# f407.net
KiCad netlist of a schematic drawn in EasyEDA Pro
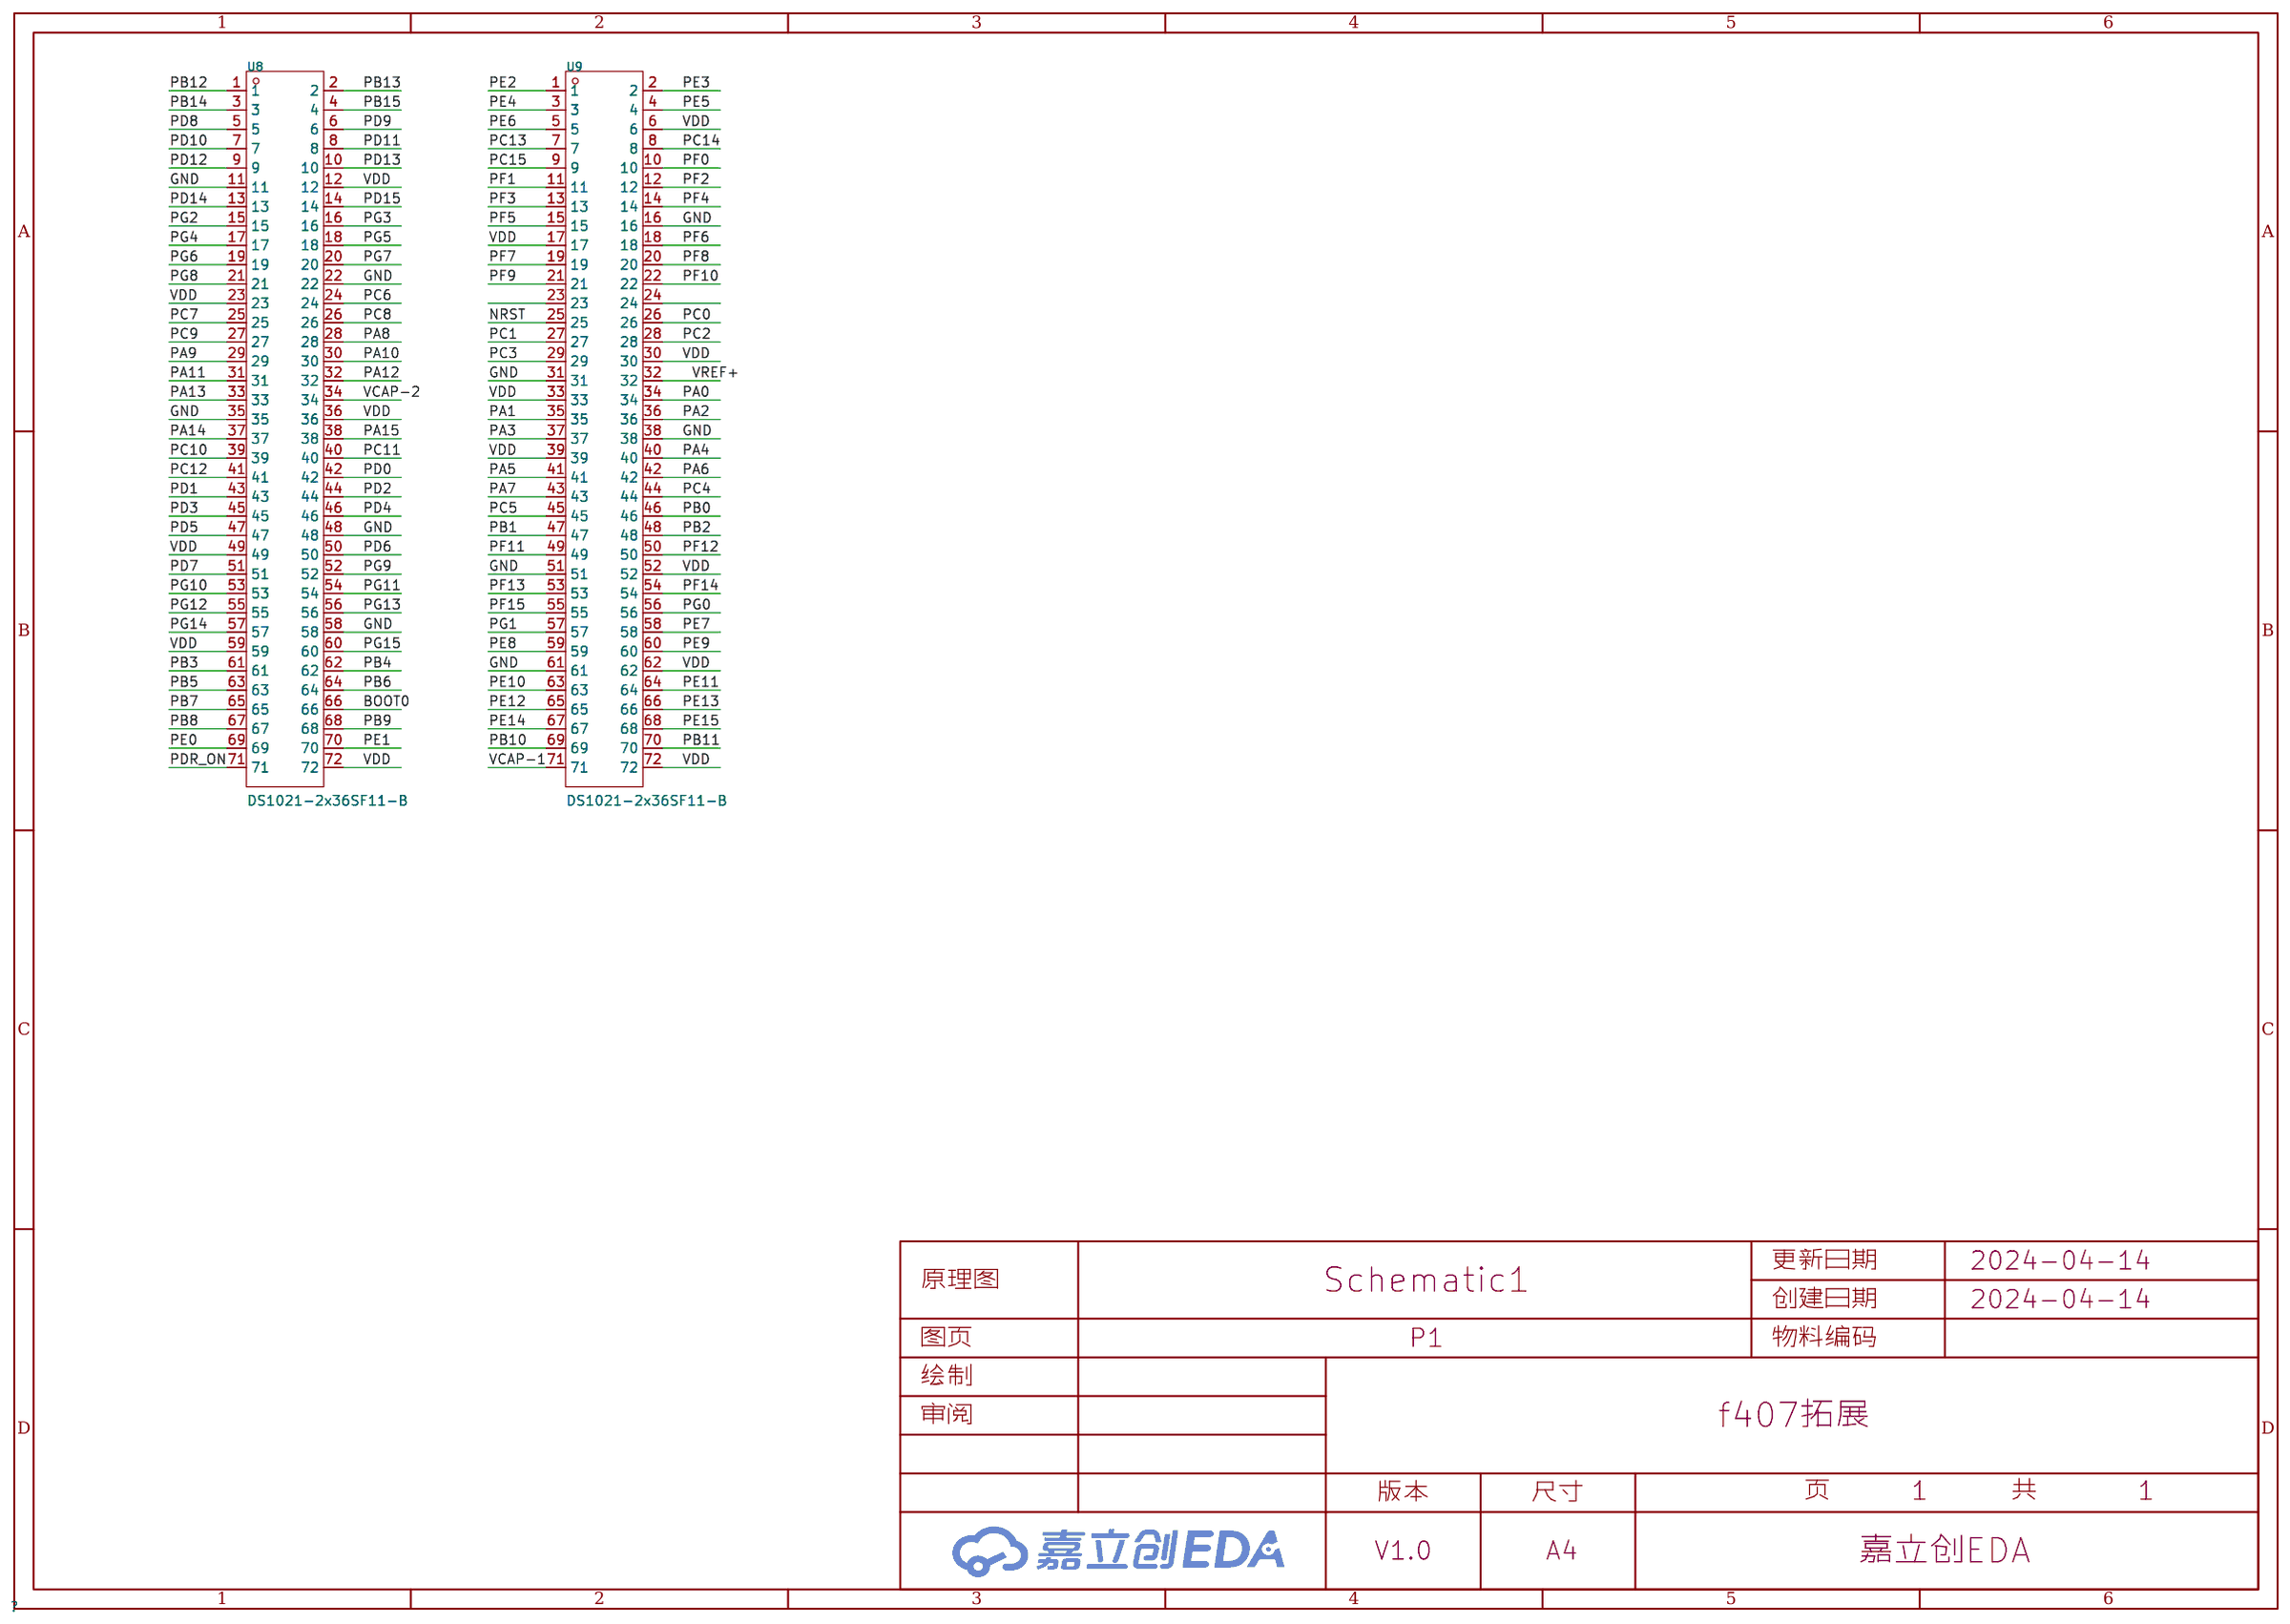
[diagram p0: schematic sheet]

(export (version "E")
  (design (tool "Eeschema 10.0.6"))
  (components
    (comp (ref "U8")
      (value "DS1021-2x36SF11-B")
      (footprint "easyedapro:HDR-TH_72P-P2.54-V-M-R2-C36-S2.54")
      (description "插针结构:2x36P;间距:2.54mm;安装类型:直插;排数:双排;总PIN位数:72P;")
      (fields (field (name "Manufacturer") "CONNFLY"))
      (libsource (lib "easyedapro") (part "DS1021-2X36SF11-B"))
    )
    (comp (ref "U9")
      (value "DS1021-2x36SF11-B")
      (footprint "easyedapro:HDR-TH_72P-P2.54-V-M-R2-C36-S2.54")
      (description "插针结构:2x36P;间距:2.54mm;安装类型:直插;排数:双排;总PIN位数:72P;")
      (fields (field (name "Manufacturer") "CONNFLY"))
      (libsource (lib "easyedapro") (part "DS1021-2X36SF11-B"))
    )
  )
  (nets
    (net (code "1") (name "/BOOT0") (class "Default")
      (node (ref "U8") (pin "66") (pinfunction "66_66") (pintype "input"))
    )
    (net (code "2") (name "/GND") (class "Default")
      (node (ref "U8") (pin "11") (pinfunction "11_11") (pintype "input"))
      (node (ref "U8") (pin "22") (pinfunction "22_22") (pintype "input"))
      (node (ref "U8") (pin "35") (pinfunction "35_35") (pintype "input"))
      (node (ref "U8") (pin "48") (pinfunction "48_48") (pintype "input"))
      (node (ref "U8") (pin "58") (pinfunction "58_58") (pintype "input"))
      (node (ref "U9") (pin "16") (pinfunction "16_16") (pintype "input"))
      (node (ref "U9") (pin "31") (pinfunction "31_31") (pintype "input"))
      (node (ref "U9") (pin "38") (pinfunction "38_38") (pintype "input"))
      (node (ref "U9") (pin "51") (pinfunction "51_51") (pintype "input"))
      (node (ref "U9") (pin "61") (pinfunction "61_61") (pintype "input"))
    )
    (net (code "3") (name "/NRST") (class "Default")
      (node (ref "U9") (pin "25") (pinfunction "25_25") (pintype "input"))
    )
    (net (code "4") (name "/PA0") (class "Default")
      (node (ref "U9") (pin "34") (pinfunction "34_34") (pintype "input"))
    )
    (net (code "5") (name "/PA1") (class "Default")
      (node (ref "U9") (pin "35") (pinfunction "35_35") (pintype "input"))
    )
    (net (code "6") (name "/PA2") (class "Default")
      (node (ref "U9") (pin "36") (pinfunction "36_36") (pintype "input"))
    )
    (net (code "7") (name "/PA3") (class "Default")
      (node (ref "U9") (pin "37") (pinfunction "37_37") (pintype "input"))
    )
    (net (code "8") (name "/PA4") (class "Default")
      (node (ref "U9") (pin "40") (pinfunction "40_40") (pintype "input"))
    )
    (net (code "9") (name "/PA5") (class "Default")
      (node (ref "U9") (pin "41") (pinfunction "41_41") (pintype "input"))
    )
    (net (code "10") (name "/PA6") (class "Default")
      (node (ref "U9") (pin "42") (pinfunction "42_42") (pintype "input"))
    )
    (net (code "11") (name "/PA7") (class "Default")
      (node (ref "U9") (pin "43") (pinfunction "43_43") (pintype "input"))
    )
    (net (code "12") (name "/PA8") (class "Default")
      (node (ref "U8") (pin "28") (pinfunction "28_28") (pintype "input"))
    )
    (net (code "13") (name "/PA9") (class "Default")
      (node (ref "U8") (pin "29") (pinfunction "29_29") (pintype "input"))
    )
    (net (code "14") (name "/PA10") (class "Default")
      (node (ref "U8") (pin "30") (pinfunction "30_30") (pintype "input"))
    )
    (net (code "15") (name "/PA11") (class "Default")
      (node (ref "U8") (pin "31") (pinfunction "31_31") (pintype "input"))
    )
    (net (code "16") (name "/PA12") (class "Default")
      (node (ref "U8") (pin "32") (pinfunction "32_32") (pintype "input"))
    )
    (net (code "17") (name "/PA13") (class "Default")
      (node (ref "U8") (pin "33") (pinfunction "33_33") (pintype "input"))
    )
    (net (code "18") (name "/PA14") (class "Default")
      (node (ref "U8") (pin "37") (pinfunction "37_37") (pintype "input"))
    )
    (net (code "19") (name "/PA15") (class "Default")
      (node (ref "U8") (pin "38") (pinfunction "38_38") (pintype "input"))
    )
    (net (code "20") (name "/PB0") (class "Default")
      (node (ref "U9") (pin "46") (pinfunction "46_46") (pintype "input"))
    )
    (net (code "21") (name "/PB1") (class "Default")
      (node (ref "U9") (pin "47") (pinfunction "47_47") (pintype "input"))
    )
    (net (code "22") (name "/PB2") (class "Default")
      (node (ref "U9") (pin "48") (pinfunction "48_48") (pintype "input"))
    )
    (net (code "23") (name "/PB3") (class "Default")
      (node (ref "U8") (pin "61") (pinfunction "61_61") (pintype "input"))
    )
    (net (code "24") (name "/PB4") (class "Default")
      (node (ref "U8") (pin "62") (pinfunction "62_62") (pintype "input"))
    )
    (net (code "25") (name "/PB5") (class "Default")
      (node (ref "U8") (pin "63") (pinfunction "63_63") (pintype "input"))
    )
    (net (code "26") (name "/PB6") (class "Default")
      (node (ref "U8") (pin "64") (pinfunction "64_64") (pintype "input"))
    )
    (net (code "27") (name "/PB7") (class "Default")
      (node (ref "U8") (pin "65") (pinfunction "65_65") (pintype "input"))
    )
    (net (code "28") (name "/PB8") (class "Default")
      (node (ref "U8") (pin "67") (pinfunction "67_67") (pintype "input"))
    )
    (net (code "29") (name "/PB9") (class "Default")
      (node (ref "U8") (pin "68") (pinfunction "68_68") (pintype "input"))
    )
    (net (code "30") (name "/PB10") (class "Default")
      (node (ref "U9") (pin "69") (pinfunction "69_69") (pintype "input"))
    )
    (net (code "31") (name "/PB11") (class "Default")
      (node (ref "U9") (pin "70") (pinfunction "70_70") (pintype "input"))
    )
    (net (code "32") (name "/PB12") (class "Default")
      (node (ref "U8") (pin "1") (pinfunction "1_1") (pintype "input"))
    )
    (net (code "33") (name "/PB13") (class "Default")
      (node (ref "U8") (pin "2") (pinfunction "2_2") (pintype "input"))
    )
    (net (code "34") (name "/PB14") (class "Default")
      (node (ref "U8") (pin "3") (pinfunction "3_3") (pintype "input"))
    )
    (net (code "35") (name "/PB15") (class "Default")
      (node (ref "U8") (pin "4") (pinfunction "4_4") (pintype "input"))
    )
    (net (code "36") (name "/PC0") (class "Default")
      (node (ref "U9") (pin "26") (pinfunction "26_26") (pintype "input"))
    )
    (net (code "37") (name "/PC1") (class "Default")
      (node (ref "U9") (pin "27") (pinfunction "27_27") (pintype "input"))
    )
    (net (code "38") (name "/PC2") (class "Default")
      (node (ref "U9") (pin "28") (pinfunction "28_28") (pintype "input"))
    )
    (net (code "39") (name "/PC3") (class "Default")
      (node (ref "U9") (pin "29") (pinfunction "29_29") (pintype "input"))
    )
    (net (code "40") (name "/PC4") (class "Default")
      (node (ref "U9") (pin "44") (pinfunction "44_44") (pintype "input"))
    )
    (net (code "41") (name "/PC5") (class "Default")
      (node (ref "U9") (pin "45") (pinfunction "45_45") (pintype "input"))
    )
    (net (code "42") (name "/PC6") (class "Default")
      (node (ref "U8") (pin "24") (pinfunction "24_24") (pintype "input"))
    )
    (net (code "43") (name "/PC7") (class "Default")
      (node (ref "U8") (pin "25") (pinfunction "25_25") (pintype "input"))
    )
    (net (code "44") (name "/PC8") (class "Default")
      (node (ref "U8") (pin "26") (pinfunction "26_26") (pintype "input"))
    )
    (net (code "45") (name "/PC9") (class "Default")
      (node (ref "U8") (pin "27") (pinfunction "27_27") (pintype "input"))
    )
    (net (code "46") (name "/PC10") (class "Default")
      (node (ref "U8") (pin "39") (pinfunction "39_39") (pintype "input"))
    )
    (net (code "47") (name "/PC11") (class "Default")
      (node (ref "U8") (pin "40") (pinfunction "40_40") (pintype "input"))
    )
    (net (code "48") (name "/PC12") (class "Default")
      (node (ref "U8") (pin "41") (pinfunction "41_41") (pintype "input"))
    )
    (net (code "49") (name "/PC13") (class "Default")
      (node (ref "U9") (pin "7") (pinfunction "7_7") (pintype "input"))
    )
    (net (code "50") (name "/PC14") (class "Default")
      (node (ref "U9") (pin "8") (pinfunction "8_8") (pintype "input"))
    )
    (net (code "51") (name "/PC15") (class "Default")
      (node (ref "U9") (pin "9") (pinfunction "9_9") (pintype "input"))
    )
    (net (code "52") (name "/PD0") (class "Default")
      (node (ref "U8") (pin "42") (pinfunction "42_42") (pintype "input"))
    )
    (net (code "53") (name "/PD1") (class "Default")
      (node (ref "U8") (pin "43") (pinfunction "43_43") (pintype "input"))
    )
    (net (code "54") (name "/PD2") (class "Default")
      (node (ref "U8") (pin "44") (pinfunction "44_44") (pintype "input"))
    )
    (net (code "55") (name "/PD3") (class "Default")
      (node (ref "U8") (pin "45") (pinfunction "45_45") (pintype "input"))
    )
    (net (code "56") (name "/PD4") (class "Default")
      (node (ref "U8") (pin "46") (pinfunction "46_46") (pintype "input"))
    )
    (net (code "57") (name "/PD5") (class "Default")
      (node (ref "U8") (pin "47") (pinfunction "47_47") (pintype "input"))
    )
    (net (code "58") (name "/PD6") (class "Default")
      (node (ref "U8") (pin "50") (pinfunction "50_50") (pintype "input"))
    )
    (net (code "59") (name "/PD7") (class "Default")
      (node (ref "U8") (pin "51") (pinfunction "51_51") (pintype "input"))
    )
    (net (code "60") (name "/PD8") (class "Default")
      (node (ref "U8") (pin "5") (pinfunction "5_5") (pintype "input"))
    )
    (net (code "61") (name "/PD9") (class "Default")
      (node (ref "U8") (pin "6") (pinfunction "6_6") (pintype "input"))
    )
    (net (code "62") (name "/PD10") (class "Default")
      (node (ref "U8") (pin "7") (pinfunction "7_7") (pintype "input"))
    )
    (net (code "63") (name "/PD11") (class "Default")
      (node (ref "U8") (pin "8") (pinfunction "8_8") (pintype "input"))
    )
    (net (code "64") (name "/PD12") (class "Default")
      (node (ref "U8") (pin "9") (pinfunction "9_9") (pintype "input"))
    )
    (net (code "65") (name "/PD13") (class "Default")
      (node (ref "U8") (pin "10") (pinfunction "10_10") (pintype "input"))
    )
    (net (code "66") (name "/PD14") (class "Default")
      (node (ref "U8") (pin "13") (pinfunction "13_13") (pintype "input"))
    )
    (net (code "67") (name "/PD15") (class "Default")
      (node (ref "U8") (pin "14") (pinfunction "14_14") (pintype "input"))
    )
    (net (code "68") (name "/PDR_ON") (class "Default")
      (node (ref "U8") (pin "71") (pinfunction "71_71") (pintype "input"))
    )
    (net (code "69") (name "/PE0") (class "Default")
      (node (ref "U8") (pin "69") (pinfunction "69_69") (pintype "input"))
    )
    (net (code "70") (name "/PE1") (class "Default")
      (node (ref "U8") (pin "70") (pinfunction "70_70") (pintype "input"))
    )
    (net (code "71") (name "/PE2") (class "Default")
      (node (ref "U9") (pin "1") (pinfunction "1_1") (pintype "input"))
    )
    (net (code "72") (name "/PE3") (class "Default")
      (node (ref "U9") (pin "2") (pinfunction "2_2") (pintype "input"))
    )
    (net (code "73") (name "/PE4") (class "Default")
      (node (ref "U9") (pin "3") (pinfunction "3_3") (pintype "input"))
    )
    (net (code "74") (name "/PE5") (class "Default")
      (node (ref "U9") (pin "4") (pinfunction "4_4") (pintype "input"))
    )
    (net (code "75") (name "/PE6") (class "Default")
      (node (ref "U9") (pin "5") (pinfunction "5_5") (pintype "input"))
    )
    (net (code "76") (name "/PE7") (class "Default")
      (node (ref "U9") (pin "58") (pinfunction "58_58") (pintype "input"))
    )
    (net (code "77") (name "/PE8") (class "Default")
      (node (ref "U9") (pin "59") (pinfunction "59_59") (pintype "input"))
    )
    (net (code "78") (name "/PE9") (class "Default")
      (node (ref "U9") (pin "60") (pinfunction "60_60") (pintype "input"))
    )
    (net (code "79") (name "/PE10") (class "Default")
      (node (ref "U9") (pin "63") (pinfunction "63_63") (pintype "input"))
    )
    (net (code "80") (name "/PE11") (class "Default")
      (node (ref "U9") (pin "64") (pinfunction "64_64") (pintype "input"))
    )
    (net (code "81") (name "/PE12") (class "Default")
      (node (ref "U9") (pin "65") (pinfunction "65_65") (pintype "input"))
    )
    (net (code "82") (name "/PE13") (class "Default")
      (node (ref "U9") (pin "66") (pinfunction "66_66") (pintype "input"))
    )
    (net (code "83") (name "/PE14") (class "Default")
      (node (ref "U9") (pin "67") (pinfunction "67_67") (pintype "input"))
    )
    (net (code "84") (name "/PE15") (class "Default")
      (node (ref "U9") (pin "68") (pinfunction "68_68") (pintype "input"))
    )
    (net (code "85") (name "/PF0") (class "Default")
      (node (ref "U9") (pin "10") (pinfunction "10_10") (pintype "input"))
    )
    (net (code "86") (name "/PF1") (class "Default")
      (node (ref "U9") (pin "11") (pinfunction "11_11") (pintype "input"))
    )
    (net (code "87") (name "/PF2") (class "Default")
      (node (ref "U9") (pin "12") (pinfunction "12_12") (pintype "input"))
    )
    (net (code "88") (name "/PF3") (class "Default")
      (node (ref "U9") (pin "13") (pinfunction "13_13") (pintype "input"))
    )
    (net (code "89") (name "/PF4") (class "Default")
      (node (ref "U9") (pin "14") (pinfunction "14_14") (pintype "input"))
    )
    (net (code "90") (name "/PF5") (class "Default")
      (node (ref "U9") (pin "15") (pinfunction "15_15") (pintype "input"))
    )
    (net (code "91") (name "/PF6") (class "Default")
      (node (ref "U9") (pin "18") (pinfunction "18_18") (pintype "input"))
    )
    (net (code "92") (name "/PF7") (class "Default")
      (node (ref "U9") (pin "19") (pinfunction "19_19") (pintype "input"))
    )
    (net (code "93") (name "/PF8") (class "Default")
      (node (ref "U9") (pin "20") (pinfunction "20_20") (pintype "input"))
    )
    (net (code "94") (name "/PF9") (class "Default")
      (node (ref "U9") (pin "21") (pinfunction "21_21") (pintype "input"))
    )
    (net (code "95") (name "/PF10") (class "Default")
      (node (ref "U9") (pin "22") (pinfunction "22_22") (pintype "input"))
    )
    (net (code "96") (name "/PF11") (class "Default")
      (node (ref "U9") (pin "49") (pinfunction "49_49") (pintype "input"))
    )
    (net (code "97") (name "/PF12") (class "Default")
      (node (ref "U9") (pin "50") (pinfunction "50_50") (pintype "input"))
    )
    (net (code "98") (name "/PF13") (class "Default")
      (node (ref "U9") (pin "53") (pinfunction "53_53") (pintype "input"))
    )
    (net (code "99") (name "/PF14") (class "Default")
      (node (ref "U9") (pin "54") (pinfunction "54_54") (pintype "input"))
    )
    (net (code "100") (name "/PF15") (class "Default")
      (node (ref "U9") (pin "55") (pinfunction "55_55") (pintype "input"))
    )
    (net (code "101") (name "/PG0") (class "Default")
      (node (ref "U9") (pin "56") (pinfunction "56_56") (pintype "input"))
    )
    (net (code "102") (name "/PG1") (class "Default")
      (node (ref "U9") (pin "57") (pinfunction "57_57") (pintype "input"))
    )
    (net (code "103") (name "/PG2") (class "Default")
      (node (ref "U8") (pin "15") (pinfunction "15_15") (pintype "input"))
    )
    (net (code "104") (name "/PG3") (class "Default")
      (node (ref "U8") (pin "16") (pinfunction "16_16") (pintype "input"))
    )
    (net (code "105") (name "/PG4") (class "Default")
      (node (ref "U8") (pin "17") (pinfunction "17_17") (pintype "input"))
    )
    (net (code "106") (name "/PG5") (class "Default")
      (node (ref "U8") (pin "18") (pinfunction "18_18") (pintype "input"))
    )
    (net (code "107") (name "/PG6") (class "Default")
      (node (ref "U8") (pin "19") (pinfunction "19_19") (pintype "input"))
    )
    (net (code "108") (name "/PG7") (class "Default")
      (node (ref "U8") (pin "20") (pinfunction "20_20") (pintype "input"))
    )
    (net (code "109") (name "/PG8") (class "Default")
      (node (ref "U8") (pin "21") (pinfunction "21_21") (pintype "input"))
    )
    (net (code "110") (name "/PG9") (class "Default")
      (node (ref "U8") (pin "52") (pinfunction "52_52") (pintype "input"))
    )
    (net (code "111") (name "/PG10") (class "Default")
      (node (ref "U8") (pin "53") (pinfunction "53_53") (pintype "input"))
    )
    (net (code "112") (name "/PG11") (class "Default")
      (node (ref "U8") (pin "54") (pinfunction "54_54") (pintype "input"))
    )
    (net (code "113") (name "/PG12") (class "Default")
      (node (ref "U8") (pin "55") (pinfunction "55_55") (pintype "input"))
    )
    (net (code "114") (name "/PG13") (class "Default")
      (node (ref "U8") (pin "56") (pinfunction "56_56") (pintype "input"))
    )
    (net (code "115") (name "/PG14") (class "Default")
      (node (ref "U8") (pin "57") (pinfunction "57_57") (pintype "input"))
    )
    (net (code "116") (name "/PG15") (class "Default")
      (node (ref "U8") (pin "60") (pinfunction "60_60") (pintype "input"))
    )
    (net (code "117") (name "/VCAP-1") (class "Default")
      (node (ref "U9") (pin "71") (pinfunction "71_71") (pintype "input"))
    )
    (net (code "118") (name "/VCAP-2") (class "Default")
      (node (ref "U8") (pin "34") (pinfunction "34_34") (pintype "input"))
    )
    (net (code "119") (name "/VDD") (class "Default")
      (node (ref "U8") (pin "12") (pinfunction "12_12") (pintype "input"))
      (node (ref "U8") (pin "23") (pinfunction "23_23") (pintype "input"))
      (node (ref "U8") (pin "36") (pinfunction "36_36") (pintype "input"))
      (node (ref "U8") (pin "49") (pinfunction "49_49") (pintype "input"))
      (node (ref "U8") (pin "59") (pinfunction "59_59") (pintype "input"))
      (node (ref "U8") (pin "72") (pinfunction "72_72") (pintype "input"))
      (node (ref "U9") (pin "17") (pinfunction "17_17") (pintype "input"))
      (node (ref "U9") (pin "30") (pinfunction "30_30") (pintype "input"))
      (node (ref "U9") (pin "33") (pinfunction "33_33") (pintype "input"))
      (node (ref "U9") (pin "39") (pinfunction "39_39") (pintype "input"))
      (node (ref "U9") (pin "52") (pinfunction "52_52") (pintype "input"))
      (node (ref "U9") (pin "6") (pinfunction "6_6") (pintype "input"))
      (node (ref "U9") (pin "62") (pinfunction "62_62") (pintype "input"))
      (node (ref "U9") (pin "72") (pinfunction "72_72") (pintype "input"))
    )
    (net (code "120") (name "/VREF+") (class "Default")
      (node (ref "U9") (pin "32") (pinfunction "32_32") (pintype "input"))
    )
    (net (code "121") (name "unconnected-(U9-Pad23)") (class "Default")
      (node (ref "U9") (pin "23") (pinfunction "23_23") (pintype "input"))
    )
    (net (code "122") (name "unconnected-(U9-Pad24)") (class "Default")
      (node (ref "U9") (pin "24") (pinfunction "24_24") (pintype "input"))
    )
  )
)
